# CAn_tranceiver.net
KiCad netlist of a schematic drawn in Altium Designer
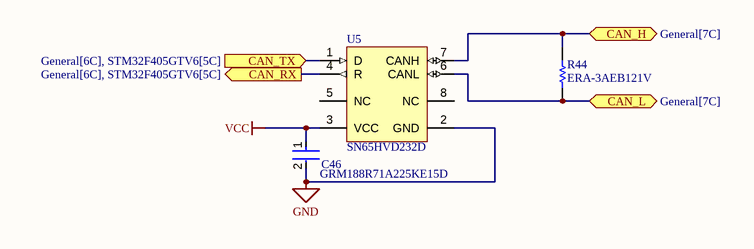
[diagram p0: CAn tranceiver.SchDoc]

(export (version "E")
  (design (tool "Eeschema 10.0.6"))
  (components
    (comp (ref "C46")
      (value "GRM188R71A225KE15D")
      (footprint "FP-GRM188-0_1-e0_2_0_5-MFG")
      (description "Chip Multilayer Ceramic Capacitors for General Purpose, 0603, 2.2uF, X7R, 15%, 10%, 10V")
      (fields (field (name "VOLTAGE") "10V") (field (name "TOLERANCE") "10%"))
      (libsource (lib "Altium Content Vault") (part "11868f565c42a9108669ba33697ecf6"))
    )
    (comp (ref "R44")
      (value "ERA-3AEB121V")
      (footprint "RESC1608X55X30NL20T20")
      (fields (field (name "MANUFACTURER") "Panasonic"))
      (libsource (lib "Altium Content Vault") (part "RES"))
    )
    (comp (ref "U5")
      (value "SN65HVD232D")
      (footprint "D0008A_L")
      (description "3.3 V CAN Transceiver, 17 mA, -40 to 85 degC, 8-pin SOIC (D), Green (RoHS & no Sb/Br)")
      (fields (field (name "MANUFACTURER") "Texas Instruments"))
      (libsource (lib "Altium Content Vault") (part "TI-SN65HVD232-SOIC_D-8"))
    )
  )
  (nets
    (net (code "1") (name "/CAN_H") (class "Default")
      (node (ref "R44") (pin "1") (pinfunction "1_1") (pintype "passive"))
      (node (ref "U5") (pin "7") (pinfunction "CANH_7") (pintype "bidirectional"))
    )
    (net (code "2") (name "/CAN_L") (class "Default")
      (node (ref "R44") (pin "2") (pinfunction "2_2") (pintype "passive"))
      (node (ref "U5") (pin "6") (pinfunction "CANL_6") (pintype "bidirectional"))
    )
    (net (code "3") (name "/CAN_RX") (class "Default")
      (node (ref "U5") (pin "4") (pinfunction "R_4") (pintype "output"))
    )
    (net (code "4") (name "/CAN_TX") (class "Default")
      (node (ref "U5") (pin "1") (pinfunction "D_1") (pintype "input"))
    )
    (net (code "5") (name "GND") (class "Default")
      (node (ref "C46") (pin "2") (pinfunction "2_2") (pintype "passive"))
      (node (ref "U5") (pin "2") (pinfunction "GND_2") (pintype "power_in"))
    )
    (net (code "6") (name "VCC") (class "Default")
      (node (ref "C46") (pin "1") (pinfunction "1_1") (pintype "passive"))
      (node (ref "U5") (pin "3") (pinfunction "VCC_3") (pintype "power_in"))
    )
    (net (code "7") (name "unconnected-(U5-NC-Pad5)") (class "Default")
      (node (ref "U5") (pin "5") (pinfunction "NC_5") (pintype "passive"))
    )
    (net (code "8") (name "unconnected-(U5-NC-Pad8)") (class "Default")
      (node (ref "U5") (pin "8") (pinfunction "NC_8") (pintype "passive"))
    )
  )
)
